# M040E.net
KiCad netlist of a schematic drawn in EAGLE
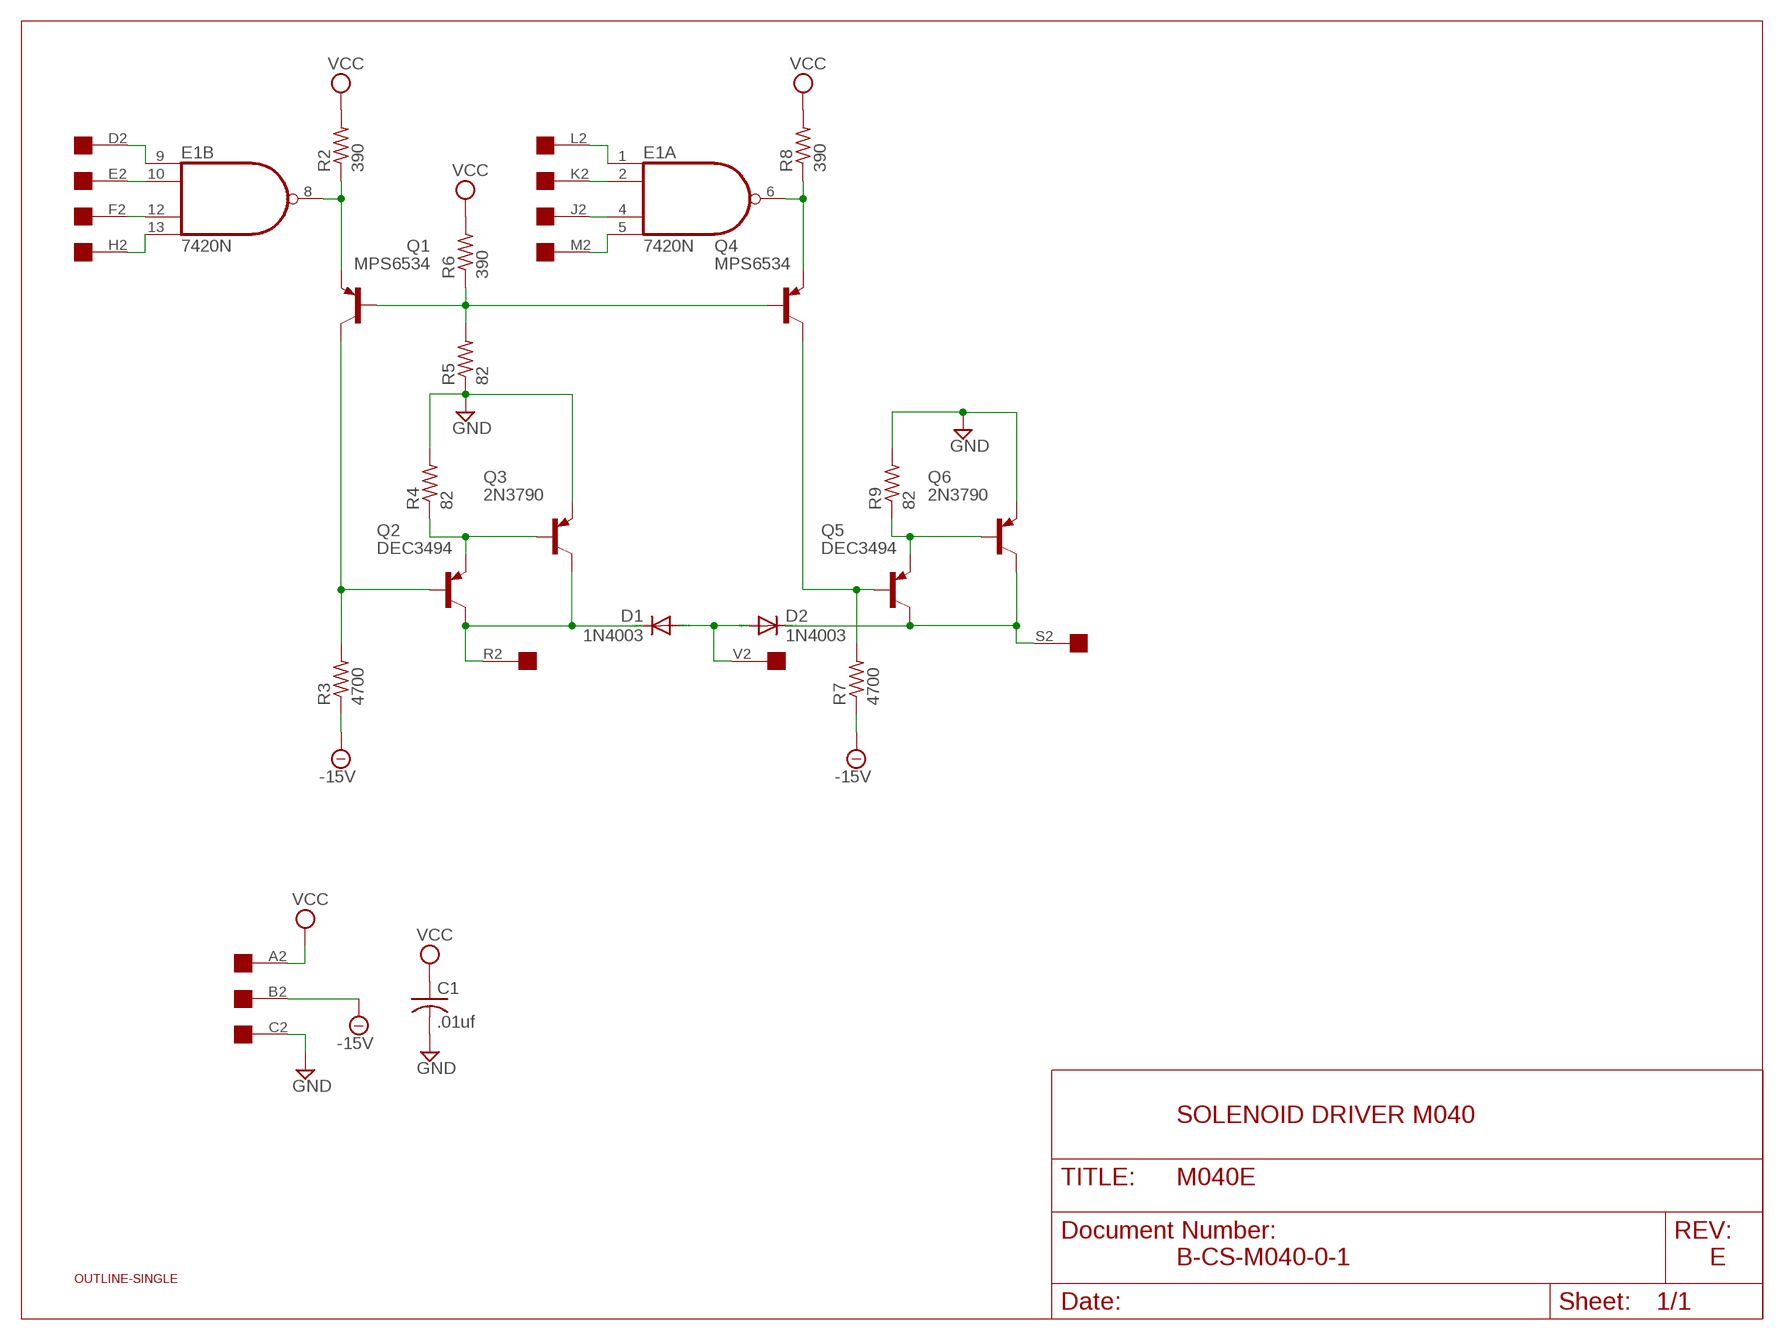
[diagram p0: schematic, sheet 1]

(export (version "E")
  (design (tool "Eeschema 10.0.6"))
  (components
    (comp (ref "C1")
      (value ".01uf")
      (footprint "eagle-import:C050-025X075")
      (libsource (lib "eagle-import") (part "C-US050-025X075"))
    )
    (comp (ref "D1")
      (value "1N4003")
      (footprint "eagle-import:DO41-10")
      (libsource (lib "eagle-import") (part "1N4004"))
    )
    (comp (ref "D2")
      (value "1N4003")
      (footprint "eagle-import:DO41-10")
      (libsource (lib "eagle-import") (part "1N4004"))
    )
    (comp (ref "E1")
      (value "7420N")
      (footprint "eagle-import:DIL14")
      (libsource (lib "eagle-import") (part "7420NS"))
    )
    (comp (ref "Q1")
      (value "MPS6534")
      (footprint "eagle-import:TO39")
      (libsource (lib "eagle-import") (part "-PNP-TO39-EBC2N2904"))
    )
    (comp (ref "Q2")
      (value "DEC3494")
      (footprint "eagle-import:TO39")
      (libsource (lib "eagle-import") (part "-PNP-TO39-EBC2N2904"))
    )
    (comp (ref "Q3")
      (value "2N3790")
      (footprint "eagle-import:TO3")
      (libsource (lib "eagle-import") (part "-PNP-TO3"))
    )
    (comp (ref "Q4")
      (value "MPS6534")
      (footprint "eagle-import:TO39")
      (libsource (lib "eagle-import") (part "-PNP-TO39-EBC2N2904"))
    )
    (comp (ref "Q5")
      (value "DEC3494")
      (footprint "eagle-import:TO39")
      (libsource (lib "eagle-import") (part "-PNP-TO39-EBC2N2904"))
    )
    (comp (ref "Q6")
      (value "2N3790")
      (footprint "eagle-import:TO3")
      (libsource (lib "eagle-import") (part "-PNP-TO3"))
    )
    (comp (ref "R2")
      (value "390")
      (footprint "eagle-import:0207_10")
      (libsource (lib "eagle-import") (part "R-US_0207/10"))
    )
    (comp (ref "R3")
      (value "4700")
      (footprint "eagle-import:0207_10")
      (libsource (lib "eagle-import") (part "R-US_0207/10"))
    )
    (comp (ref "R4")
      (value "82")
      (footprint "eagle-import:0207_10")
      (libsource (lib "eagle-import") (part "R-US_0207/10"))
    )
    (comp (ref "R5")
      (value "82")
      (footprint "eagle-import:0207_10")
      (libsource (lib "eagle-import") (part "R-US_0207/10"))
    )
    (comp (ref "R6")
      (value "390")
      (footprint "eagle-import:0207_10")
      (libsource (lib "eagle-import") (part "R-US_0207/10"))
    )
    (comp (ref "R7")
      (value "4700")
      (footprint "eagle-import:0207_10")
      (libsource (lib "eagle-import") (part "R-US_0207/10"))
    )
    (comp (ref "R8")
      (value "390")
      (footprint "eagle-import:0207_10")
      (libsource (lib "eagle-import") (part "R-US_0207/10"))
    )
    (comp (ref "R9")
      (value "82")
      (footprint "eagle-import:0207_10")
      (libsource (lib "eagle-import") (part "R-US_0207/10"))
    )
    (comp (ref "U$1")
      (value "OUTLINE-SINGLE")
      (footprint "eagle-import:SINGLE")
      (libsource (lib "eagle-import") (part "OUTLINE-SINGLE"))
    )
    (comp (ref "U$2")
      (value "EDGE-1")
      (footprint "eagle-import:EDGE-CON1")
      (libsource (lib "eagle-import") (part "EDGE-1"))
    )
  )
  (nets
    (net (code "1") (name "-15V") (class "Default")
      (node (ref "R3") (pin "1") (pinfunction "1_1") (pintype "passive"))
      (node (ref "R7") (pin "1") (pinfunction "1_1") (pintype "passive"))
      (node (ref "U$2") (pin "B2") (pinfunction "1_B2") (pintype "bidirectional"))
    )
    (net (code "2") (name "GND") (class "Default")
      (node (ref "C1") (pin "2") (pinfunction "2_2") (pintype "passive"))
      (node (ref "Q3") (pin "E") (pinfunction "E_E") (pintype "passive"))
      (node (ref "Q6") (pin "E") (pinfunction "E_E") (pintype "passive"))
      (node (ref "R4") (pin "2") (pinfunction "2_2") (pintype "passive"))
      (node (ref "R5") (pin "1") (pinfunction "1_1") (pintype "passive"))
      (node (ref "R9") (pin "2") (pinfunction "2_2") (pintype "passive"))
      (node (ref "U$2") (pin "C2") (pinfunction "1_C2") (pintype "bidirectional"))
    )
    (net (code "3") (name "Net-(E1A-I0)") (class "Default")
      (node (ref "E1") (pin "1") (pinfunction "I0_1") (pintype "input"))
      (node (ref "U$2") (pin "L2") (pinfunction "1_L2") (pintype "bidirectional"))
    )
    (net (code "4") (name "Net-(E1A-I1)") (class "Default")
      (node (ref "E1") (pin "2") (pinfunction "I1_2") (pintype "input"))
      (node (ref "U$2") (pin "K2") (pinfunction "1_K2") (pintype "bidirectional"))
    )
    (net (code "5") (name "Net-(E1A-I2)") (class "Default")
      (node (ref "E1") (pin "4") (pinfunction "I2_4") (pintype "input"))
      (node (ref "U$2") (pin "J2") (pinfunction "1_J2") (pintype "bidirectional"))
    )
    (net (code "6") (name "Net-(E1A-I3)") (class "Default")
      (node (ref "E1") (pin "5") (pinfunction "I3_5") (pintype "input"))
      (node (ref "U$2") (pin "M2") (pinfunction "1_M2") (pintype "bidirectional"))
    )
    (net (code "7") (name "Net-(E1A-O)") (class "Default")
      (node (ref "E1") (pin "6") (pinfunction "O_6") (pintype "output"))
      (node (ref "Q4") (pin "1") (pinfunction "E_1") (pintype "passive"))
      (node (ref "R8") (pin "1") (pinfunction "1_1") (pintype "passive"))
    )
    (net (code "8") (name "Net-(E1B-I0)") (class "Default")
      (node (ref "E1") (pin "9") (pinfunction "I0_9") (pintype "input"))
      (node (ref "U$2") (pin "D2") (pinfunction "1_D2") (pintype "bidirectional"))
    )
    (net (code "9") (name "Net-(E1B-I1)") (class "Default")
      (node (ref "E1") (pin "10") (pinfunction "I1_10") (pintype "input"))
      (node (ref "U$2") (pin "E2") (pinfunction "1_E2") (pintype "bidirectional"))
    )
    (net (code "10") (name "Net-(E1B-I2)") (class "Default")
      (node (ref "E1") (pin "12") (pinfunction "I2_12") (pintype "input"))
      (node (ref "U$2") (pin "F2") (pinfunction "1_F2") (pintype "bidirectional"))
    )
    (net (code "11") (name "Net-(E1B-I3)") (class "Default")
      (node (ref "E1") (pin "13") (pinfunction "I3_13") (pintype "input"))
      (node (ref "U$2") (pin "H2") (pinfunction "1_H2") (pintype "bidirectional"))
    )
    (net (code "12") (name "Net-(E1B-O)") (class "Default")
      (node (ref "E1") (pin "8") (pinfunction "O_8") (pintype "output"))
      (node (ref "Q1") (pin "1") (pinfunction "E_1") (pintype "passive"))
      (node (ref "R2") (pin "1") (pinfunction "1_1") (pintype "passive"))
    )
    (net (code "13") (name "Net-(Q1-B)") (class "Default")
      (node (ref "Q1") (pin "2") (pinfunction "B_2") (pintype "passive"))
      (node (ref "Q4") (pin "2") (pinfunction "B_2") (pintype "passive"))
      (node (ref "R5") (pin "2") (pinfunction "2_2") (pintype "passive"))
      (node (ref "R6") (pin "1") (pinfunction "1_1") (pintype "passive"))
    )
    (net (code "14") (name "Net-(Q1-C)") (class "Default")
      (node (ref "Q1") (pin "3") (pinfunction "C_3") (pintype "passive"))
      (node (ref "Q2") (pin "2") (pinfunction "B_2") (pintype "passive"))
      (node (ref "R3") (pin "2") (pinfunction "2_2") (pintype "passive"))
    )
    (net (code "15") (name "Net-(Q2-C)") (class "Default")
      (node (ref "D1") (pin "C") (pinfunction "C_C") (pintype "passive"))
      (node (ref "Q2") (pin "3") (pinfunction "C_3") (pintype "passive"))
      (node (ref "Q3") (pin "C") (pinfunction "C_C") (pintype "passive"))
      (node (ref "U$2") (pin "R2") (pinfunction "1_R2") (pintype "bidirectional"))
    )
    (net (code "16") (name "Net-(Q2-E)") (class "Default")
      (node (ref "Q2") (pin "1") (pinfunction "E_1") (pintype "passive"))
      (node (ref "Q3") (pin "B") (pinfunction "B_B") (pintype "passive"))
      (node (ref "R4") (pin "1") (pinfunction "1_1") (pintype "passive"))
    )
    (net (code "17") (name "Net-(Q4-C)") (class "Default")
      (node (ref "Q4") (pin "3") (pinfunction "C_3") (pintype "passive"))
      (node (ref "Q5") (pin "2") (pinfunction "B_2") (pintype "passive"))
      (node (ref "R7") (pin "2") (pinfunction "2_2") (pintype "passive"))
    )
    (net (code "18") (name "Net-(Q5-C)") (class "Default")
      (node (ref "D2") (pin "C") (pinfunction "C_C") (pintype "passive"))
      (node (ref "Q5") (pin "3") (pinfunction "C_3") (pintype "passive"))
      (node (ref "Q6") (pin "C") (pinfunction "C_C") (pintype "passive"))
      (node (ref "U$2") (pin "S2") (pinfunction "1_S2") (pintype "bidirectional"))
    )
    (net (code "19") (name "Net-(Q5-E)") (class "Default")
      (node (ref "Q5") (pin "1") (pinfunction "E_1") (pintype "passive"))
      (node (ref "Q6") (pin "B") (pinfunction "B_B") (pintype "passive"))
      (node (ref "R9") (pin "1") (pinfunction "1_1") (pintype "passive"))
    )
    (net (code "20") (name "Net-(U$2R-1)") (class "Default")
      (node (ref "D1") (pin "A") (pinfunction "A_A") (pintype "passive"))
      (node (ref "D2") (pin "A") (pinfunction "A_A") (pintype "passive"))
      (node (ref "U$2") (pin "V2") (pinfunction "1_V2") (pintype "bidirectional"))
    )
    (net (code "21") (name "VCC") (class "Default")
      (node (ref "C1") (pin "1") (pinfunction "1_1") (pintype "passive"))
      (node (ref "R2") (pin "2") (pinfunction "2_2") (pintype "passive"))
      (node (ref "R6") (pin "2") (pinfunction "2_2") (pintype "passive"))
      (node (ref "R8") (pin "2") (pinfunction "2_2") (pintype "passive"))
      (node (ref "U$2") (pin "A2") (pinfunction "1_A2") (pintype "bidirectional"))
    )
  )
)
